# ob-xa-2p-lpf.net
KiCad netlist of a schematic drawn in EAGLE
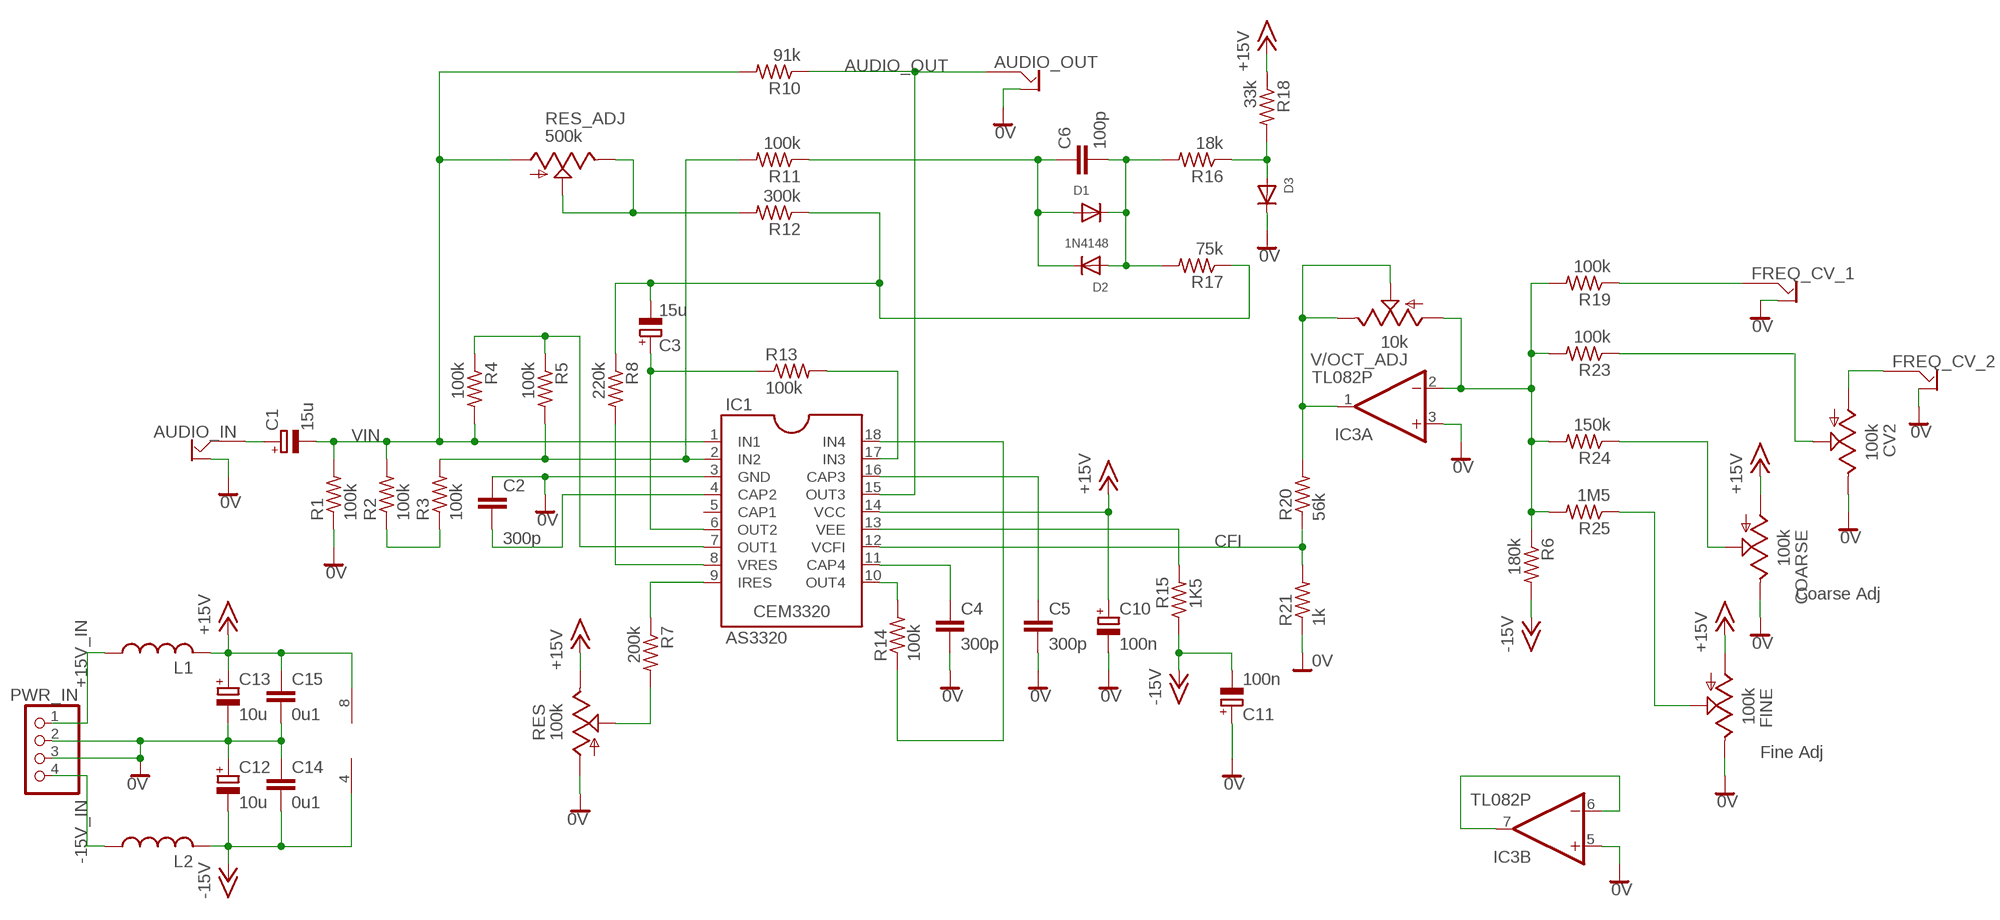
[diagram p0: schematic, sheet 1]

(export (version "E")
  (design (tool "Eeschema 10.0.6"))
  (components
    (comp (ref "AUDIO_IN")
      (value "OFFBOARD2JACKALT")
      (footprint "eagle-import:OFFBOARD2JACKALT")
      (libsource (lib "eagle-import") (part "OFFBOARD2JACKALT"))
    )
    (comp (ref "AUDIO_OUT")
      (value "OFFBOARD2JACKALT")
      (footprint "eagle-import:OFFBOARD2JACKALT")
      (libsource (lib "eagle-import") (part "OFFBOARD2JACKALT"))
    )
    (comp (ref "C1")
      (value "15u")
      (footprint "eagle-import:E1,8-4")
      (libsource (lib "eagle-import") (part "CPOL-EUE1.8-4"))
    )
    (comp (ref "C2")
      (value "300p")
      (footprint "eagle-import:C050-025X075")
      (libsource (lib "eagle-import") (part "C-EU050-025X075"))
    )
    (comp (ref "C3")
      (value "15u")
      (footprint "eagle-import:E1,8-4")
      (libsource (lib "eagle-import") (part "CPOL-EUE1.8-4"))
    )
    (comp (ref "C4")
      (value "300p")
      (footprint "eagle-import:C050-025X075")
      (libsource (lib "eagle-import") (part "C-EU050-025X075"))
    )
    (comp (ref "C5")
      (value "300p")
      (footprint "eagle-import:C050-025X075")
      (libsource (lib "eagle-import") (part "C-EU050-025X075"))
    )
    (comp (ref "C6")
      (value "100p")
      (footprint "eagle-import:C050-025X075")
      (libsource (lib "eagle-import") (part "C-EU050-025X075"))
    )
    (comp (ref "C10")
      (value "100n")
      (footprint "eagle-import:E1,8-4")
      (libsource (lib "eagle-import") (part "CPOL-EUE1.8-4"))
    )
    (comp (ref "C11")
      (value "100n")
      (footprint "eagle-import:E1,8-4")
      (libsource (lib "eagle-import") (part "CPOL-EUE1.8-4"))
    )
    (comp (ref "C12")
      (value "10u")
      (footprint "eagle-import:E1,8-4")
      (libsource (lib "eagle-import") (part "CPOL-EUE1.8-4"))
    )
    (comp (ref "C13")
      (value "10u")
      (footprint "eagle-import:E1,8-4")
      (libsource (lib "eagle-import") (part "CPOL-EUE1.8-4"))
    )
    (comp (ref "C14")
      (value "0u1")
      (footprint "eagle-import:C050-025X075")
      (libsource (lib "eagle-import") (part "C-EU050-025X075"))
    )
    (comp (ref "C15")
      (value "0u1")
      (footprint "eagle-import:C050-025X075")
      (libsource (lib "eagle-import") (part "C-EU050-025X075"))
    )
    (comp (ref "COARSE")
      (value "100k")
      (footprint "eagle-import:B64Y")
      (libsource (lib "eagle-import") (part "TRIM_US-B64Y"))
    )
    (comp (ref "CV2")
      (value "100k")
      (footprint "eagle-import:B64Y")
      (libsource (lib "eagle-import") (part "TRIM_US-B64Y"))
    )
    (comp (ref "D1")
      (value "1N4148")
      (footprint "eagle-import:DO-1N4148")
      (libsource (lib "eagle-import") (part "DIODEDO-1N4148"))
    )
    (comp (ref "D2")
      (value "1N4148")
      (footprint "eagle-import:DO-1N4148")
      (libsource (lib "eagle-import") (part "DIODEDO-1N4148"))
    )
    (comp (ref "D3")
      (value "1N4148")
      (footprint "eagle-import:DO-1N4148")
      (libsource (lib "eagle-import") (part "DIODEDO-1N4148"))
    )
    (comp (ref "FINE")
      (value "100k")
      (footprint "eagle-import:B64Y")
      (libsource (lib "eagle-import") (part "TRIM_US-B64Y"))
    )
    (comp (ref "FREQ_CV_1")
      (value "OFFBOARD2JACKALT")
      (footprint "eagle-import:OFFBOARD2JACKALT")
      (libsource (lib "eagle-import") (part "OFFBOARD2JACKALT"))
    )
    (comp (ref "FREQ_CV_2")
      (value "OFFBOARD2JACKALT")
      (footprint "eagle-import:OFFBOARD2JACKALT")
      (libsource (lib "eagle-import") (part "OFFBOARD2JACKALT"))
    )
    (comp (ref "IC1")
      (value "AS3320")
      (footprint "eagle-import:DIL18")
      (libsource (lib "eagle-import") (part "AS3320"))
    )
    (comp (ref "IC3")
      (value "TL082P")
      (footprint "eagle-import:DIL08")
      (libsource (lib "eagle-import") (part "TL082P"))
    )
    (comp (ref "L1")
      (value "L-US0207/10")
      (footprint "eagle-import:0207_10")
      (libsource (lib "eagle-import") (part "L-US0207/10"))
    )
    (comp (ref "L2")
      (value "L-US0207/10")
      (footprint "eagle-import:0207_10")
      (libsource (lib "eagle-import") (part "L-US0207/10"))
    )
    (comp (ref "PWR_IN")
      (value "PINHD-1X4")
      (footprint "eagle-import:1X04")
      (libsource (lib "eagle-import") (part "PINHD-1X4"))
    )
    (comp (ref "R1")
      (value "100k")
      (footprint "eagle-import:0207_10")
      (libsource (lib "eagle-import") (part "R-US_0207/10"))
    )
    (comp (ref "R2")
      (value "100k")
      (footprint "eagle-import:0207_10")
      (libsource (lib "eagle-import") (part "R-US_0207/10"))
    )
    (comp (ref "R3")
      (value "100k")
      (footprint "eagle-import:0207_10")
      (libsource (lib "eagle-import") (part "R-US_0207/10"))
    )
    (comp (ref "R4")
      (value "100k")
      (footprint "eagle-import:0207_10")
      (libsource (lib "eagle-import") (part "R-US_0207/10"))
    )
    (comp (ref "R5")
      (value "100k")
      (footprint "eagle-import:0207_10")
      (libsource (lib "eagle-import") (part "R-US_0207/10"))
    )
    (comp (ref "R6")
      (value "180k")
      (footprint "eagle-import:0207_10")
      (libsource (lib "eagle-import") (part "R-US_0207/10"))
    )
    (comp (ref "R7")
      (value "200k")
      (footprint "eagle-import:0207_10")
      (libsource (lib "eagle-import") (part "R-US_0207/10"))
    )
    (comp (ref "R8")
      (value "220k")
      (footprint "eagle-import:0207_10")
      (libsource (lib "eagle-import") (part "R-US_0207/10"))
    )
    (comp (ref "R10")
      (value "91k")
      (footprint "eagle-import:0207_10")
      (libsource (lib "eagle-import") (part "R-US_0207/10"))
    )
    (comp (ref "R11")
      (value "100k")
      (footprint "eagle-import:0207_10")
      (libsource (lib "eagle-import") (part "R-US_0207/10"))
    )
    (comp (ref "R12")
      (value "300k")
      (footprint "eagle-import:0207_10")
      (libsource (lib "eagle-import") (part "R-US_0207/10"))
    )
    (comp (ref "R13")
      (value "100k")
      (footprint "eagle-import:0207_10")
      (libsource (lib "eagle-import") (part "R-US_0207/10"))
    )
    (comp (ref "R14")
      (value "100k")
      (footprint "eagle-import:0207_10")
      (libsource (lib "eagle-import") (part "R-US_0207/10"))
    )
    (comp (ref "R15")
      (value "1K5")
      (footprint "eagle-import:0207_10")
      (libsource (lib "eagle-import") (part "R-US_0207/10"))
    )
    (comp (ref "R16")
      (value "18k")
      (footprint "eagle-import:0207_10")
      (libsource (lib "eagle-import") (part "R-US_0207/10"))
    )
    (comp (ref "R17")
      (value "75k")
      (footprint "eagle-import:0207_10")
      (libsource (lib "eagle-import") (part "R-US_0207/10"))
    )
    (comp (ref "R18")
      (value "33k")
      (footprint "eagle-import:0207_10")
      (libsource (lib "eagle-import") (part "R-US_0207/10"))
    )
    (comp (ref "R19")
      (value "100k")
      (footprint "eagle-import:0207_10")
      (libsource (lib "eagle-import") (part "R-US_0207/10"))
    )
    (comp (ref "R20")
      (value "56k")
      (footprint "eagle-import:0207_10")
      (libsource (lib "eagle-import") (part "R-US_0207/10"))
    )
    (comp (ref "R21")
      (value "1k")
      (footprint "eagle-import:0207_10")
      (libsource (lib "eagle-import") (part "R-US_0207/10"))
    )
    (comp (ref "R23")
      (value "100k")
      (footprint "eagle-import:0207_10")
      (libsource (lib "eagle-import") (part "R-US_0207/10"))
    )
    (comp (ref "R24")
      (value "150k")
      (footprint "eagle-import:0207_10")
      (libsource (lib "eagle-import") (part "R-US_0207/10"))
    )
    (comp (ref "R25")
      (value "1M5")
      (footprint "eagle-import:0207_10")
      (libsource (lib "eagle-import") (part "R-US_0207/10"))
    )
    (comp (ref "RES")
      (value "100k")
      (footprint "eagle-import:B64Y")
      (libsource (lib "eagle-import") (part "TRIM_US-B64Y"))
    )
    (comp (ref "RES_ADJ")
      (value "500k")
      (footprint "eagle-import:S63P")
      (libsource (lib "eagle-import") (part "TRIM_US-S63P"))
    )
    (comp (ref "V/OCT_ADJ")
      (value "10k")
      (footprint "eagle-import:S63P")
      (libsource (lib "eagle-import") (part "TRIM_US-S63P"))
    )
  )
  (nets
    (net (code "1") (name "+15V") (class "Default")
      (node (ref "C10") (pin "+") (pinfunction "+_+") (pintype "passive"))
      (node (ref "C13") (pin "+") (pinfunction "+_+") (pintype "passive"))
      (node (ref "C15") (pin "1") (pinfunction "1_1") (pintype "passive"))
      (node (ref "COARSE") (pin "A") (pinfunction "A_A") (pintype "passive"))
      (node (ref "FINE") (pin "A") (pinfunction "A_A") (pintype "passive"))
      (node (ref "IC1") (pin "14") (pinfunction "VCC_14") (pintype "passive"))
      (node (ref "IC3") (pin "8") (pinfunction "V+_8") (pintype "power_in"))
      (node (ref "L1") (pin "2") (pinfunction "2_2") (pintype "passive"))
      (node (ref "R18") (pin "1") (pinfunction "1_1") (pintype "passive"))
      (node (ref "RES") (pin "E") (pinfunction "E_E") (pintype "passive"))
    )
    (net (code "2") (name "-15V") (class "Default")
      (node (ref "C11") (pin "-") (pinfunction "-_-") (pintype "passive"))
      (node (ref "C12") (pin "-") (pinfunction "-_-") (pintype "passive"))
      (node (ref "C14") (pin "2") (pinfunction "2_2") (pintype "passive"))
      (node (ref "IC3") (pin "4") (pinfunction "V-_4") (pintype "power_in"))
      (node (ref "L2") (pin "2") (pinfunction "2_2") (pintype "passive"))
      (node (ref "R15") (pin "1") (pinfunction "1_1") (pintype "passive"))
      (node (ref "R6") (pin "2") (pinfunction "2_2") (pintype "passive"))
    )
    (net (code "3") (name "/+15V_IN") (class "Default")
      (node (ref "L1") (pin "1") (pinfunction "1_1") (pintype "passive"))
      (node (ref "PWR_IN") (pin "1") (pinfunction "1_1") (pintype "passive"))
    )
    (net (code "4") (name "/-15V_IN") (class "Default")
      (node (ref "L2") (pin "1") (pinfunction "1_1") (pintype "passive"))
      (node (ref "PWR_IN") (pin "4") (pinfunction "4_4") (pintype "passive"))
    )
    (net (code "5") (name "/AUDIO_OUT") (class "Default")
      (node (ref "AUDIO_OUT") (pin "SIGNAL") (pinfunction "SIGNAL_SIGNAL") (pintype "passive"))
      (node (ref "IC1") (pin "15") (pinfunction "OUT3_15") (pintype "passive"))
      (node (ref "R10") (pin "1") (pinfunction "1_1") (pintype "passive"))
    )
    (net (code "6") (name "/CFI") (class "Default")
      (node (ref "IC1") (pin "12") (pinfunction "VCFI_12") (pintype "passive"))
      (node (ref "R20") (pin "1") (pinfunction "1_1") (pintype "passive"))
      (node (ref "R21") (pin "2") (pinfunction "2_2") (pintype "passive"))
    )
    (net (code "7") (name "/VIN") (class "Default")
      (node (ref "C1") (pin "-") (pinfunction "-_-") (pintype "passive"))
      (node (ref "IC1") (pin "1") (pinfunction "IN1_1") (pintype "passive"))
      (node (ref "R1") (pin "2") (pinfunction "2_2") (pintype "passive"))
      (node (ref "R10") (pin "2") (pinfunction "2_2") (pintype "passive"))
      (node (ref "R2") (pin "2") (pinfunction "2_2") (pintype "passive"))
      (node (ref "R4") (pin "2") (pinfunction "2_2") (pintype "passive"))
      (node (ref "RES_ADJ") (pin "A") (pinfunction "A_A") (pintype "passive"))
    )
    (net (code "8") (name "0V") (class "Default")
      (node (ref "AUDIO_IN") (pin "GND") (pinfunction "GND_GND") (pintype "passive"))
      (node (ref "AUDIO_OUT") (pin "GND") (pinfunction "GND_GND") (pintype "passive"))
      (node (ref "C10") (pin "-") (pinfunction "-_-") (pintype "passive"))
      (node (ref "C11") (pin "+") (pinfunction "+_+") (pintype "passive"))
      (node (ref "C12") (pin "+") (pinfunction "+_+") (pintype "passive"))
      (node (ref "C13") (pin "-") (pinfunction "-_-") (pintype "passive"))
      (node (ref "C14") (pin "1") (pinfunction "1_1") (pintype "passive"))
      (node (ref "C15") (pin "2") (pinfunction "2_2") (pintype "passive"))
      (node (ref "C2") (pin "1") (pinfunction "1_1") (pintype "passive"))
      (node (ref "C4") (pin "2") (pinfunction "2_2") (pintype "passive"))
      (node (ref "C5") (pin "2") (pinfunction "2_2") (pintype "passive"))
      (node (ref "COARSE") (pin "E") (pinfunction "E_E") (pintype "passive"))
      (node (ref "CV2") (pin "E") (pinfunction "E_E") (pintype "passive"))
      (node (ref "D3") (pin "C") (pinfunction "C_C") (pintype "passive"))
      (node (ref "FINE") (pin "E") (pinfunction "E_E") (pintype "passive"))
      (node (ref "FREQ_CV_1") (pin "GND") (pinfunction "GND_GND") (pintype "passive"))
      (node (ref "FREQ_CV_2") (pin "GND") (pinfunction "GND_GND") (pintype "passive"))
      (node (ref "IC1") (pin "3") (pinfunction "GND_3") (pintype "passive"))
      (node (ref "IC3") (pin "3") (pinfunction "+IN_3") (pintype "input"))
      (node (ref "IC3") (pin "5") (pinfunction "+IN_5") (pintype "input"))
      (node (ref "PWR_IN") (pin "2") (pinfunction "2_2") (pintype "passive"))
      (node (ref "PWR_IN") (pin "3") (pinfunction "3_3") (pintype "passive"))
      (node (ref "R1") (pin "1") (pinfunction "1_1") (pintype "passive"))
      (node (ref "R21") (pin "1") (pinfunction "1_1") (pintype "passive"))
      (node (ref "RES") (pin "A") (pinfunction "A_A") (pintype "passive"))
    )
    (net (code "9") (name "Net-(AUDIO_IN-PadSIGNAL)") (class "Default")
      (node (ref "AUDIO_IN") (pin "SIGNAL") (pinfunction "SIGNAL_SIGNAL") (pintype "passive"))
      (node (ref "C1") (pin "+") (pinfunction "+_+") (pintype "passive"))
    )
    (net (code "10") (name "Net-(C3-Pad-)") (class "Default")
      (node (ref "C3") (pin "-") (pinfunction "-_-") (pintype "passive"))
      (node (ref "R12") (pin "1") (pinfunction "1_1") (pintype "passive"))
      (node (ref "R17") (pin "1") (pinfunction "1_1") (pintype "passive"))
      (node (ref "R8") (pin "1") (pinfunction "1_1") (pintype "passive"))
    )
    (net (code "11") (name "Net-(C6-Pad1)") (class "Default")
      (node (ref "C6") (pin "1") (pinfunction "1_1") (pintype "passive"))
      (node (ref "D1") (pin "A") (pinfunction "A_A") (pintype "passive"))
      (node (ref "D2") (pin "C") (pinfunction "C_C") (pintype "passive"))
      (node (ref "R11") (pin "1") (pinfunction "1_1") (pintype "passive"))
    )
    (net (code "12") (name "Net-(C6-Pad2)") (class "Default")
      (node (ref "C6") (pin "2") (pinfunction "2_2") (pintype "passive"))
      (node (ref "D1") (pin "C") (pinfunction "C_C") (pintype "passive"))
      (node (ref "D2") (pin "A") (pinfunction "A_A") (pintype "passive"))
      (node (ref "R16") (pin "2") (pinfunction "2_2") (pintype "passive"))
      (node (ref "R17") (pin "2") (pinfunction "2_2") (pintype "passive"))
    )
    (net (code "13") (name "Net-(COARSE-PadS)") (class "Default")
      (node (ref "COARSE") (pin "S") (pinfunction "S_S") (pintype "passive"))
      (node (ref "R24") (pin "1") (pinfunction "1_1") (pintype "passive"))
    )
    (net (code "14") (name "Net-(CV2-PadA)") (class "Default")
      (node (ref "CV2") (pin "A") (pinfunction "A_A") (pintype "passive"))
      (node (ref "FREQ_CV_2") (pin "SIGNAL") (pinfunction "SIGNAL_SIGNAL") (pintype "passive"))
    )
    (net (code "15") (name "Net-(CV2-PadS)") (class "Default")
      (node (ref "CV2") (pin "S") (pinfunction "S_S") (pintype "passive"))
      (node (ref "R23") (pin "1") (pinfunction "1_1") (pintype "passive"))
    )
    (net (code "16") (name "Net-(D3-PadA)") (class "Default")
      (node (ref "D3") (pin "A") (pinfunction "A_A") (pintype "passive"))
      (node (ref "R16") (pin "1") (pinfunction "1_1") (pintype "passive"))
      (node (ref "R18") (pin "2") (pinfunction "2_2") (pintype "passive"))
    )
    (net (code "17") (name "Net-(FINE-PadS)") (class "Default")
      (node (ref "FINE") (pin "S") (pinfunction "S_S") (pintype "passive"))
      (node (ref "R25") (pin "1") (pinfunction "1_1") (pintype "passive"))
    )
    (net (code "18") (name "Net-(FREQ_CV_1-PadSIGNAL)") (class "Default")
      (node (ref "FREQ_CV_1") (pin "SIGNAL") (pinfunction "SIGNAL_SIGNAL") (pintype "passive"))
      (node (ref "R19") (pin "1") (pinfunction "1_1") (pintype "passive"))
    )
    (net (code "19") (name "Net-(IC1-CAP2)") (class "Default")
      (node (ref "C2") (pin "2") (pinfunction "2_2") (pintype "passive"))
      (node (ref "IC1") (pin "4") (pinfunction "CAP2_4") (pintype "passive"))
    )
    (net (code "20") (name "Net-(IC1-CAP3)") (class "Default")
      (node (ref "C5") (pin "1") (pinfunction "1_1") (pintype "passive"))
      (node (ref "IC1") (pin "16") (pinfunction "CAP3_16") (pintype "passive"))
    )
    (net (code "21") (name "Net-(IC1-CAP4)") (class "Default")
      (node (ref "C4") (pin "1") (pinfunction "1_1") (pintype "passive"))
      (node (ref "IC1") (pin "11") (pinfunction "CAP4_11") (pintype "passive"))
    )
    (net (code "22") (name "Net-(IC1-IN2)") (class "Default")
      (node (ref "IC1") (pin "2") (pinfunction "IN2_2") (pintype "passive"))
      (node (ref "R11") (pin "2") (pinfunction "2_2") (pintype "passive"))
      (node (ref "R3") (pin "2") (pinfunction "2_2") (pintype "passive"))
      (node (ref "R5") (pin "2") (pinfunction "2_2") (pintype "passive"))
    )
    (net (code "23") (name "Net-(IC1-IN3)") (class "Default")
      (node (ref "IC1") (pin "17") (pinfunction "IN3_17") (pintype "passive"))
      (node (ref "R13") (pin "2") (pinfunction "2_2") (pintype "passive"))
    )
    (net (code "24") (name "Net-(IC1-IN4)") (class "Default")
      (node (ref "IC1") (pin "18") (pinfunction "IN4_18") (pintype "passive"))
      (node (ref "R14") (pin "1") (pinfunction "1_1") (pintype "passive"))
    )
    (net (code "25") (name "Net-(IC1-IRES)") (class "Default")
      (node (ref "IC1") (pin "9") (pinfunction "IRES_9") (pintype "passive"))
      (node (ref "R7") (pin "1") (pinfunction "1_1") (pintype "passive"))
    )
    (net (code "26") (name "Net-(IC1-OUT1)") (class "Default")
      (node (ref "IC1") (pin "7") (pinfunction "OUT1_7") (pintype "passive"))
      (node (ref "R4") (pin "1") (pinfunction "1_1") (pintype "passive"))
      (node (ref "R5") (pin "1") (pinfunction "1_1") (pintype "passive"))
    )
    (net (code "27") (name "Net-(IC1-OUT2)") (class "Default")
      (node (ref "C3") (pin "+") (pinfunction "+_+") (pintype "passive"))
      (node (ref "IC1") (pin "6") (pinfunction "OUT2_6") (pintype "passive"))
      (node (ref "R13") (pin "1") (pinfunction "1_1") (pintype "passive"))
    )
    (net (code "28") (name "Net-(IC1-OUT4)") (class "Default")
      (node (ref "IC1") (pin "10") (pinfunction "OUT4_10") (pintype "passive"))
      (node (ref "R14") (pin "2") (pinfunction "2_2") (pintype "passive"))
    )
    (net (code "29") (name "Net-(IC1-VEE)") (class "Default")
      (node (ref "IC1") (pin "13") (pinfunction "VEE_13") (pintype "passive"))
      (node (ref "R15") (pin "2") (pinfunction "2_2") (pintype "passive"))
    )
    (net (code "30") (name "Net-(IC1-VRES)") (class "Default")
      (node (ref "IC1") (pin "8") (pinfunction "VRES_8") (pintype "passive"))
      (node (ref "R8") (pin "2") (pinfunction "2_2") (pintype "passive"))
    )
    (net (code "31") (name "Net-(IC3A--IN)") (class "Default")
      (node (ref "IC3") (pin "2") (pinfunction "-IN_2") (pintype "input"))
      (node (ref "R19") (pin "2") (pinfunction "2_2") (pintype "passive"))
      (node (ref "R23") (pin "2") (pinfunction "2_2") (pintype "passive"))
      (node (ref "R24") (pin "2") (pinfunction "2_2") (pintype "passive"))
      (node (ref "R25") (pin "2") (pinfunction "2_2") (pintype "passive"))
      (node (ref "R6") (pin "1") (pinfunction "1_1") (pintype "passive"))
      (node (ref "V/OCT_ADJ") (pin "A") (pinfunction "A_A") (pintype "passive"))
    )
    (net (code "32") (name "Net-(IC3A-OUT)") (class "Default")
      (node (ref "IC3") (pin "1") (pinfunction "OUT_1") (pintype "output"))
      (node (ref "R20") (pin "2") (pinfunction "2_2") (pintype "passive"))
      (node (ref "V/OCT_ADJ") (pin "E") (pinfunction "E_E") (pintype "passive"))
      (node (ref "V/OCT_ADJ") (pin "S") (pinfunction "S_S") (pintype "passive"))
    )
    (net (code "33") (name "Net-(IC3B--IN)") (class "Default")
      (node (ref "IC3") (pin "6") (pinfunction "-IN_6") (pintype "input"))
      (node (ref "IC3") (pin "7") (pinfunction "OUT_7") (pintype "output"))
    )
    (net (code "34") (name "Net-(R2-Pad1)") (class "Default")
      (node (ref "R2") (pin "1") (pinfunction "1_1") (pintype "passive"))
      (node (ref "R3") (pin "1") (pinfunction "1_1") (pintype "passive"))
    )
    (net (code "35") (name "Net-(R7-Pad2)") (class "Default")
      (node (ref "R7") (pin "2") (pinfunction "2_2") (pintype "passive"))
      (node (ref "RES") (pin "S") (pinfunction "S_S") (pintype "passive"))
    )
    (net (code "36") (name "Net-(R12-Pad2)") (class "Default")
      (node (ref "R12") (pin "2") (pinfunction "2_2") (pintype "passive"))
      (node (ref "RES_ADJ") (pin "E") (pinfunction "E_E") (pintype "passive"))
      (node (ref "RES_ADJ") (pin "S") (pinfunction "S_S") (pintype "passive"))
    )
    (net (code "37") (name "unconnected-(IC1-CAP1-Pad5)") (class "Default")
      (node (ref "IC1") (pin "5") (pinfunction "CAP1_5") (pintype "passive"))
    )
  )
)
